# ray0.net
KiCad netlist of a schematic drawn in EAGLE
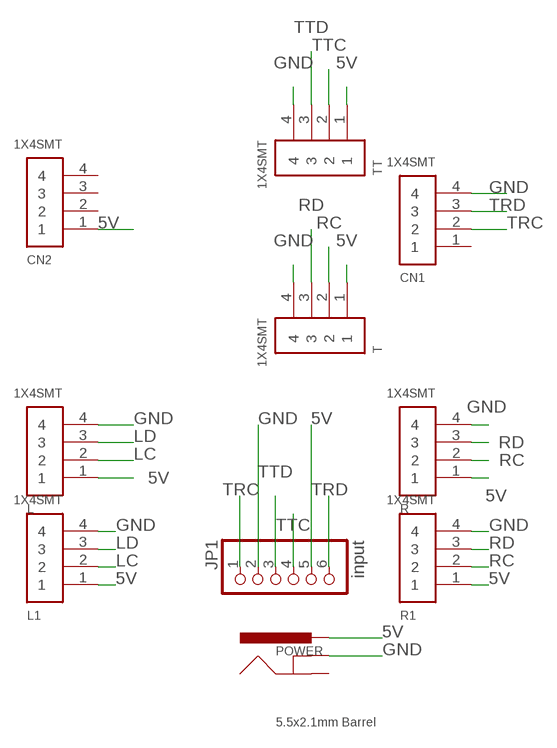
[diagram p0: schematic, sheet 1]

(export (version "E")
  (design (tool "Eeschema 10.0.6"))
  (components
    (comp (ref "CN1")
      (value "1X4SMT")
      (footprint "eagle-import:1X4-SMT")
      (libsource (lib "eagle-import") (part "1X4SMT"))
    )
    (comp (ref "CN2")
      (value "1X4SMT")
      (footprint "eagle-import:1X4-SMT")
      (libsource (lib "eagle-import") (part "1X4SMT"))
    )
    (comp (ref "JP1")
      (value "input")
      (footprint "eagle-import:1X06")
      (libsource (lib "eagle-import") (part "PINHD-1X6"))
    )
    (comp (ref "L")
      (value "1X4SMT")
      (footprint "eagle-import:1X4-SMT")
      (libsource (lib "eagle-import") (part "1X4SMT"))
    )
    (comp (ref "L1")
      (value "1X4SMT")
      (footprint "eagle-import:1X4-SMT")
      (libsource (lib "eagle-import") (part "1X4SMT"))
    )
    (comp (ref "POWER")
      (value "5.5x2.1mm Barrel")
      (footprint "eagle-import:POWER_JACK_SMD")
      (libsource (lib "eagle-import") (part "POWER_JACKSMD"))
    )
    (comp (ref "R")
      (value "1X4SMT")
      (footprint "eagle-import:1X4-SMT")
      (libsource (lib "eagle-import") (part "1X4SMT"))
    )
    (comp (ref "R1")
      (value "1X4SMT")
      (footprint "eagle-import:1X4-SMT")
      (libsource (lib "eagle-import") (part "1X4SMT"))
    )
    (comp (ref "T")
      (value "1X4SMT")
      (footprint "eagle-import:1X4-SMT")
      (libsource (lib "eagle-import") (part "1X4SMT"))
    )
    (comp (ref "TT")
      (value "1X4SMT")
      (footprint "eagle-import:1X4-SMT")
      (libsource (lib "eagle-import") (part "1X4SMT"))
    )
  )
  (nets
    (net (code "1") (name "/5V") (class "Default")
      (node (ref "CN2") (pin "1") (pinfunction "1_1") (pintype "bidirectional"))
      (node (ref "JP1") (pin "5") (pinfunction "5_5") (pintype "passive"))
      (node (ref "L") (pin "1") (pinfunction "1_1") (pintype "bidirectional"))
      (node (ref "L1") (pin "1") (pinfunction "1_1") (pintype "bidirectional"))
      (node (ref "POWER") (pin "VIN0") (pinfunction "PWR_VIN0") (pintype "bidirectional"))
      (node (ref "POWER") (pin "VIN1") (pinfunction "PWR_VIN1") (pintype "bidirectional"))
      (node (ref "R") (pin "1") (pinfunction "1_1") (pintype "bidirectional"))
      (node (ref "R1") (pin "1") (pinfunction "1_1") (pintype "bidirectional"))
      (node (ref "T") (pin "1") (pinfunction "1_1") (pintype "bidirectional"))
      (node (ref "TT") (pin "1") (pinfunction "1_1") (pintype "bidirectional"))
    )
    (net (code "2") (name "/GND") (class "Default")
      (node (ref "CN1") (pin "4") (pinfunction "4_4") (pintype "bidirectional"))
      (node (ref "JP1") (pin "2") (pinfunction "2_2") (pintype "passive"))
      (node (ref "L") (pin "4") (pinfunction "4_4") (pintype "bidirectional"))
      (node (ref "L1") (pin "4") (pinfunction "4_4") (pintype "bidirectional"))
      (node (ref "POWER") (pin "GND") (pinfunction "GNDBREAK_GND") (pintype "bidirectional"))
      (node (ref "R") (pin "4") (pinfunction "4_4") (pintype "bidirectional"))
      (node (ref "R1") (pin "4") (pinfunction "4_4") (pintype "bidirectional"))
      (node (ref "T") (pin "4") (pinfunction "4_4") (pintype "bidirectional"))
      (node (ref "TT") (pin "4") (pinfunction "4_4") (pintype "bidirectional"))
    )
    (net (code "3") (name "/LC") (class "Default")
      (node (ref "L") (pin "2") (pinfunction "2_2") (pintype "bidirectional"))
      (node (ref "L1") (pin "2") (pinfunction "2_2") (pintype "bidirectional"))
    )
    (net (code "4") (name "/LD") (class "Default")
      (node (ref "L") (pin "3") (pinfunction "3_3") (pintype "bidirectional"))
      (node (ref "L1") (pin "3") (pinfunction "3_3") (pintype "bidirectional"))
    )
    (net (code "5") (name "/RC") (class "Default")
      (node (ref "R") (pin "2") (pinfunction "2_2") (pintype "bidirectional"))
      (node (ref "R1") (pin "2") (pinfunction "2_2") (pintype "bidirectional"))
      (node (ref "T") (pin "2") (pinfunction "2_2") (pintype "bidirectional"))
    )
    (net (code "6") (name "/RD") (class "Default")
      (node (ref "R") (pin "3") (pinfunction "3_3") (pintype "bidirectional"))
      (node (ref "R1") (pin "3") (pinfunction "3_3") (pintype "bidirectional"))
      (node (ref "T") (pin "3") (pinfunction "3_3") (pintype "bidirectional"))
    )
    (net (code "7") (name "/TRC") (class "Default")
      (node (ref "CN1") (pin "2") (pinfunction "2_2") (pintype "bidirectional"))
      (node (ref "JP1") (pin "1") (pinfunction "1_1") (pintype "passive"))
    )
    (net (code "8") (name "/TRD") (class "Default")
      (node (ref "CN1") (pin "3") (pinfunction "3_3") (pintype "bidirectional"))
      (node (ref "JP1") (pin "6") (pinfunction "6_6") (pintype "passive"))
    )
    (net (code "9") (name "/TTC") (class "Default")
      (node (ref "JP1") (pin "4") (pinfunction "4_4") (pintype "passive"))
      (node (ref "TT") (pin "2") (pinfunction "2_2") (pintype "bidirectional"))
    )
    (net (code "10") (name "/TTD") (class "Default")
      (node (ref "JP1") (pin "3") (pinfunction "3_3") (pintype "passive"))
      (node (ref "TT") (pin "3") (pinfunction "3_3") (pintype "bidirectional"))
    )
    (net (code "11") (name "unconnected-(CN1-Pad1)") (class "Default")
      (node (ref "CN1") (pin "1") (pinfunction "1_1") (pintype "bidirectional"))
    )
    (net (code "12") (name "unconnected-(CN2-Pad2)") (class "Default")
      (node (ref "CN2") (pin "2") (pinfunction "2_2") (pintype "bidirectional"))
    )
    (net (code "13") (name "unconnected-(CN2-Pad3)") (class "Default")
      (node (ref "CN2") (pin "3") (pinfunction "3_3") (pintype "bidirectional"))
    )
    (net (code "14") (name "unconnected-(CN2-Pad4)") (class "Default")
      (node (ref "CN2") (pin "4") (pinfunction "4_4") (pintype "bidirectional"))
    )
    (net (code "15") (name "unconnected-(POWER-GND-PadP$4)") (class "Default")
      (node (ref "POWER") (pin "P$4") (pinfunction "GND_P$4") (pintype "bidirectional"))
    )
  )
)
